# LED_48.net
KiCad netlist of a schematic drawn in Altium Designer
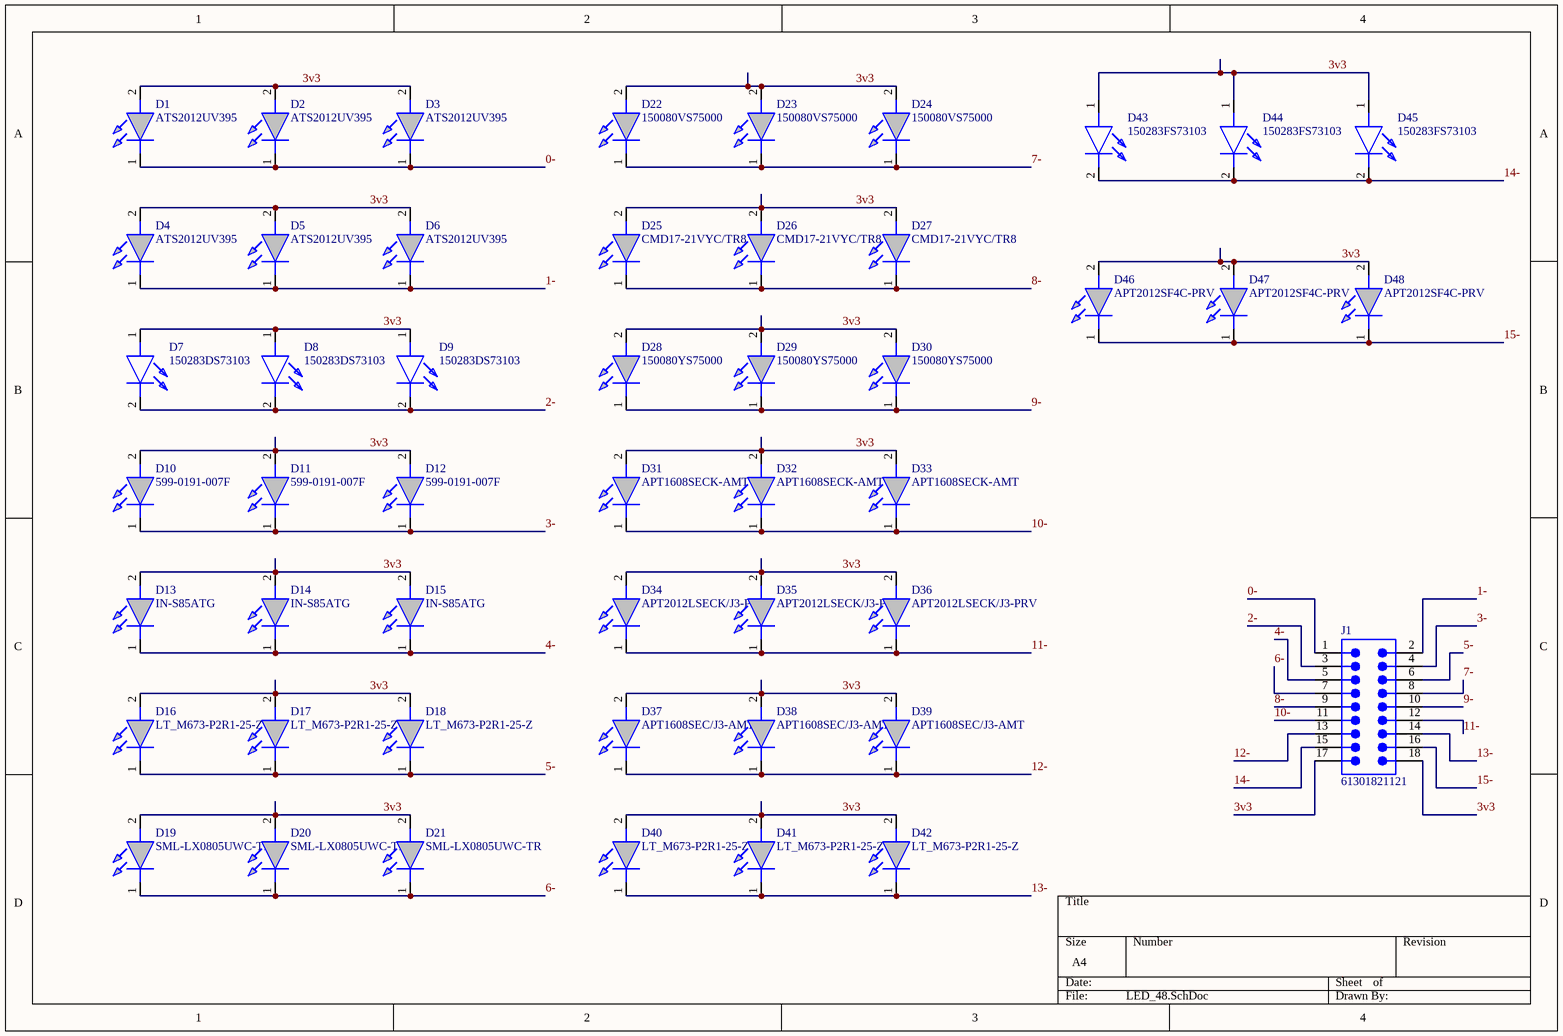
[diagram p0: LED_48.SchDoc]

(export (version "E")
  (design (tool "Eeschema 10.0.6"))
  (components
    (comp (ref "D1")
      (value "ATS2012UV395")
      (footprint "ATS2012UV395")
      (description "Standard LEDs - SMD 2x1.2mm UV SMD")
      (fields (field (name "MOUSER PART NUMBER") "604-ATS2012UV395"))
      (libsource (lib "Schlib2") (part "ATS2012UV395"))
    )
    (comp (ref "D2")
      (value "ATS2012UV395")
      (footprint "ATS2012UV395")
      (description "Standard LEDs - SMD 2x1.2mm UV SMD")
      (fields (field (name "MOUSER PART NUMBER") "604-ATS2012UV395"))
      (libsource (lib "Schlib2") (part "ATS2012UV395"))
    )
    (comp (ref "D3")
      (value "ATS2012UV395")
      (footprint "ATS2012UV395")
      (description "Standard LEDs - SMD 2x1.2mm UV SMD")
      (fields (field (name "MOUSER PART NUMBER") "604-ATS2012UV395"))
      (libsource (lib "Schlib2") (part "ATS2012UV395"))
    )
    (comp (ref "D4")
      (value "ATS2012UV395")
      (footprint "ATS2012UV395")
      (description "Standard LEDs - SMD 2x1.2mm UV SMD")
      (fields (field (name "MOUSER PART NUMBER") "604-ATS2012UV395"))
      (libsource (lib "Schlib2") (part "ATS2012UV395"))
    )
    (comp (ref "D5")
      (value "ATS2012UV395")
      (footprint "ATS2012UV395")
      (description "Standard LEDs - SMD 2x1.2mm UV SMD")
      (fields (field (name "MOUSER PART NUMBER") "604-ATS2012UV395"))
      (libsource (lib "Schlib2") (part "ATS2012UV395"))
    )
    (comp (ref "D6")
      (value "ATS2012UV395")
      (footprint "ATS2012UV395")
      (description "Standard LEDs - SMD 2x1.2mm UV SMD")
      (fields (field (name "MOUSER PART NUMBER") "604-ATS2012UV395"))
      (libsource (lib "Schlib2") (part "ATS2012UV395"))
    )
    (comp (ref "D7")
      (value "150283DS73103")
      (footprint "150283DS73103")
      (description "LED")
      (fields (field (name "MOUSER PART NUMBER") "710-150283DS73103"))
      (libsource (lib "LED_Schlib1") (part "150283DS73103"))
    )
    (comp (ref "D8")
      (value "150283DS73103")
      (footprint "150283DS73103")
      (description "LED")
      (fields (field (name "MOUSER PART NUMBER") "710-150283DS73103"))
      (libsource (lib "LED_Schlib1") (part "150283DS73103"))
    )
    (comp (ref "D9")
      (value "150283DS73103")
      (footprint "150283DS73103")
      (description "LED")
      (fields (field (name "MOUSER PART NUMBER") "710-150283DS73103"))
      (libsource (lib "LED_Schlib1") (part "150283DS73103"))
    )
    (comp (ref "D10")
      (value "599-0191-007F")
      (footprint "LEDC2012X90N")
      (description "Standard LEDs - SMD SMD 0805 BLUE")
      (fields (field (name "MOUSER PART NUMBER") "645-599-0191-007F"))
      (libsource (lib "Schlib2") (part "599-0191-007F"))
    )
    (comp (ref "D11")
      (value "599-0191-007F")
      (footprint "LEDC2012X90N")
      (description "Standard LEDs - SMD SMD 0805 BLUE")
      (fields (field (name "MOUSER PART NUMBER") "645-599-0191-007F"))
      (libsource (lib "Schlib2") (part "599-0191-007F"))
    )
    (comp (ref "D12")
      (value "599-0191-007F")
      (footprint "LEDC2012X90N")
      (description "Standard LEDs - SMD SMD 0805 BLUE")
      (fields (field (name "MOUSER PART NUMBER") "645-599-0191-007F"))
      (libsource (lib "Schlib2") (part "599-0191-007F"))
    )
    (comp (ref "D13")
      (value "IN-S85ATG")
      (footprint "LEDC2012X110N")
      (description "Standard LEDs - SMD True Green LED")
      (fields (field (name "MOUSER PART NUMBER") "743-IN-S85ATG"))
      (libsource (lib "Schlib2") (part "IN-S85ATG"))
    )
    (comp (ref "D14")
      (value "IN-S85ATG")
      (footprint "LEDC2012X110N")
      (description "Standard LEDs - SMD True Green LED")
      (fields (field (name "MOUSER PART NUMBER") "743-IN-S85ATG"))
      (libsource (lib "Schlib2") (part "IN-S85ATG"))
    )
    (comp (ref "D15")
      (value "IN-S85ATG")
      (footprint "LEDC2012X110N")
      (description "Standard LEDs - SMD True Green LED")
      (fields (field (name "MOUSER PART NUMBER") "743-IN-S85ATG"))
      (libsource (lib "Schlib2") (part "IN-S85ATG"))
    )
    (comp (ref "D16")
      (value "LT_M673-P2R1-25-Z")
      (footprint "LEDM2214X140N")
      (description "Standard LEDs - SMD True Green, 532nm 140mcd, 10mA")
      (fields
        (field (name "MOUSER PART NUMBER") "720-LTM673P2R125Z")
        (field (name "MANUFACTURER_PART_NUMBER") "LT M673-P2R1-25-Z")
      )
      (libsource (lib "Schlib2") (part "LT_M673-P2R1-25-Z"))
    )
    (comp (ref "D17")
      (value "LT_M673-P2R1-25-Z")
      (footprint "LEDM2214X140N")
      (description "Standard LEDs - SMD True Green, 532nm 140mcd, 10mA")
      (fields
        (field (name "MOUSER PART NUMBER") "720-LTM673P2R125Z")
        (field (name "MANUFACTURER_PART_NUMBER") "LT M673-P2R1-25-Z")
      )
      (libsource (lib "Schlib2") (part "LT_M673-P2R1-25-Z"))
    )
    (comp (ref "D18")
      (value "LT_M673-P2R1-25-Z")
      (footprint "LEDM2214X140N")
      (description "Standard LEDs - SMD True Green, 532nm 140mcd, 10mA")
      (fields
        (field (name "MOUSER PART NUMBER") "720-LTM673P2R125Z")
        (field (name "MANUFACTURER_PART_NUMBER") "LT M673-P2R1-25-Z")
      )
      (libsource (lib "Schlib2") (part "LT_M673-P2R1-25-Z"))
    )
    (comp (ref "D19")
      (value "SML-LX0805UWC-TR")
      (footprint "LEDC2012X80N")
      (description "Standard LEDs - SMD White, Water Clear 3.5V, 150mcd")
      (fields
        (field (name "MOUSER PART NUMBER") "645-599-0191-007F")
        (field (name "MANUFACTURER_PART_NUMBER") "599-0191-007F")
      )
      (libsource (lib "Schlib2") (part "SML-LX0805UWC-TR"))
    )
    (comp (ref "D20")
      (value "SML-LX0805UWC-TR")
      (footprint "LEDC2012X80N")
      (description "Standard LEDs - SMD White, Water Clear 3.5V, 150mcd")
      (fields
        (field (name "MOUSER PART NUMBER") "645-599-0191-007F")
        (field (name "MANUFACTURER_PART_NUMBER") "599-0191-007F")
      )
      (libsource (lib "Schlib2") (part "SML-LX0805UWC-TR"))
    )
    (comp (ref "D21")
      (value "SML-LX0805UWC-TR")
      (footprint "LEDC2012X80N")
      (description "Standard LEDs - SMD White, Water Clear 3.5V, 150mcd")
      (fields
        (field (name "MOUSER PART NUMBER") "645-599-0191-007F")
        (field (name "MANUFACTURER_PART_NUMBER") "599-0191-007F")
      )
      (libsource (lib "Schlib2") (part "SML-LX0805UWC-TR"))
    )
    (comp (ref "D22")
      (value "150080VS75000")
      (footprint "LEDC2012X80N")
      (description "Standard LEDs - SMD WL-SMCW SMDMono TpVw Waterclr 0805 BrtGrn")
      (fields
        (field (name "MOUSER PART NUMBER") "645-599-0191-007F")
        (field (name "MANUFACTURER_PART_NUMBER") "599-0191-007F")
      )
      (libsource (lib "Schlib2") (part "150080VS75000"))
    )
    (comp (ref "D23")
      (value "150080VS75000")
      (footprint "LEDC2012X80N")
      (description "Standard LEDs - SMD WL-SMCW SMDMono TpVw Waterclr 0805 BrtGrn")
      (fields
        (field (name "MOUSER PART NUMBER") "645-599-0191-007F")
        (field (name "MANUFACTURER_PART_NUMBER") "599-0191-007F")
      )
      (libsource (lib "Schlib2") (part "150080VS75000"))
    )
    (comp (ref "D24")
      (value "150080VS75000")
      (footprint "LEDC2012X80N")
      (description "Standard LEDs - SMD WL-SMCW SMDMono TpVw Waterclr 0805 BrtGrn")
      (fields
        (field (name "MOUSER PART NUMBER") "645-599-0191-007F")
        (field (name "MANUFACTURER_PART_NUMBER") "599-0191-007F")
      )
      (libsource (lib "Schlib2") (part "150080VS75000"))
    )
    (comp (ref "D25")
      (value "CMD17-21VYC/TR8")
      (footprint "LEDC2012X120N")
      (description "Standard LEDs - SMD YELLOW WATER CLEAR")
      (fields
        (field (name "MOUSER PART NUMBER") "645-599-0191-007F")
        (field (name "MANUFACTURER_PART_NUMBER") "599-0191-007F")
      )
      (libsource (lib "Schlib2") (part "CMD17-21VYC/TR8"))
    )
    (comp (ref "D26")
      (value "CMD17-21VYC/TR8")
      (footprint "LEDC2012X120N")
      (description "Standard LEDs - SMD YELLOW WATER CLEAR")
      (fields
        (field (name "MOUSER PART NUMBER") "645-599-0191-007F")
        (field (name "MANUFACTURER_PART_NUMBER") "599-0191-007F")
      )
      (libsource (lib "Schlib2") (part "CMD17-21VYC/TR8"))
    )
    (comp (ref "D27")
      (value "CMD17-21VYC/TR8")
      (footprint "LEDC2012X120N")
      (description "Standard LEDs - SMD YELLOW WATER CLEAR")
      (fields
        (field (name "MOUSER PART NUMBER") "645-599-0191-007F")
        (field (name "MANUFACTURER_PART_NUMBER") "599-0191-007F")
      )
      (libsource (lib "Schlib2") (part "CMD17-21VYC/TR8"))
    )
    (comp (ref "D28")
      (value "150080YS75000")
      (footprint "LEDC2012X80N")
      (description "Standard LEDs - SMD WL-SMCW SMDMono TpVw Waterclr 0805 Yellow")
      (fields
        (field (name "MOUSER PART NUMBER") "645-599-0191-007F")
        (field (name "MANUFACTURER_PART_NUMBER") "599-0191-007F")
      )
      (libsource (lib "Schlib2") (part "SML-LX0805UWC-TR"))
    )
    (comp (ref "D29")
      (value "150080YS75000")
      (footprint "LEDC2012X80N")
      (description "Standard LEDs - SMD WL-SMCW SMDMono TpVw Waterclr 0805 Yellow")
      (fields
        (field (name "MOUSER PART NUMBER") "645-599-0191-007F")
        (field (name "MANUFACTURER_PART_NUMBER") "599-0191-007F")
      )
      (libsource (lib "Schlib2") (part "SML-LX0805UWC-TR"))
    )
    (comp (ref "D30")
      (value "150080YS75000")
      (footprint "LEDC2012X80N")
      (description "Standard LEDs - SMD WL-SMCW SMDMono TpVw Waterclr 0805 Yellow")
      (fields
        (field (name "MOUSER PART NUMBER") "645-599-0191-007F")
        (field (name "MANUFACTURER_PART_NUMBER") "599-0191-007F")
      )
      (libsource (lib "Schlib2") (part "SML-LX0805UWC-TR"))
    )
    (comp (ref "D31")
      (value "APT1608SECK-AMT")
      (footprint "LEDC1608X85N")
      (description "Standard LEDs - SMD 1.6x0.8mm Orange")
      (fields
        (field (name "MOUSER PART NUMBER") "645-599-0191-007F")
        (field (name "MANUFACTURER_PART_NUMBER") "599-0191-007F")
      )
      (libsource (lib "Schlib2") (part "APT1608SECK-AMT"))
    )
    (comp (ref "D32")
      (value "APT1608SECK-AMT")
      (footprint "LEDC1608X85N")
      (description "Standard LEDs - SMD 1.6x0.8mm Orange")
      (fields
        (field (name "MOUSER PART NUMBER") "645-599-0191-007F")
        (field (name "MANUFACTURER_PART_NUMBER") "599-0191-007F")
      )
      (libsource (lib "Schlib2") (part "APT1608SECK-AMT"))
    )
    (comp (ref "D33")
      (value "APT1608SECK-AMT")
      (footprint "LEDC1608X85N")
      (description "Standard LEDs - SMD 1.6x0.8mm Orange")
      (fields
        (field (name "MOUSER PART NUMBER") "645-599-0191-007F")
        (field (name "MANUFACTURER_PART_NUMBER") "599-0191-007F")
      )
      (libsource (lib "Schlib2") (part "APT1608SECK-AMT"))
    )
    (comp (ref "D34")
      (value "APT2012LSECK/J3-PRV")
      (footprint "LEDC2012X75N")
      (description "Standard LEDs - SMD 2.0X1.2MM LOW CRNT")
      (fields
        (field (name "MANUFACTURER_PART_NUMBER") "ATS2012UV395")
        (field (name "MOUSER PART NUMBER") "604-ATS2012UV395")
      )
      (libsource (lib "Schlib2") (part "APT2012LSECK/J3-PRV"))
    )
    (comp (ref "D35")
      (value "APT2012LSECK/J3-PRV")
      (footprint "LEDC2012X75N")
      (description "Standard LEDs - SMD 2.0X1.2MM LOW CRNT")
      (fields
        (field (name "MANUFACTURER_PART_NUMBER") "ATS2012UV395")
        (field (name "MOUSER PART NUMBER") "604-ATS2012UV395")
      )
      (libsource (lib "Schlib2") (part "APT2012LSECK/J3-PRV"))
    )
    (comp (ref "D36")
      (value "APT2012LSECK/J3-PRV")
      (footprint "LEDC2012X75N")
      (description "Standard LEDs - SMD 2.0X1.2MM LOW CRNT")
      (fields
        (field (name "MANUFACTURER_PART_NUMBER") "ATS2012UV395")
        (field (name "MOUSER PART NUMBER") "604-ATS2012UV395")
      )
      (libsource (lib "Schlib2") (part "APT2012LSECK/J3-PRV"))
    )
    (comp (ref "D37")
      (value "APT1608SEC/J3-AMT")
      (footprint "APT1608SECJ3AMT")
      (description "Standard LEDs - SMD 1.6x0.8mm Red")
      (fields
        (field (name "MANUFACTURER_PART_NUMBER") "ATS2012UV395")
        (field (name "MOUSER PART NUMBER") "604-ATS2012UV395")
      )
      (libsource (lib "Schlib2") (part "APT1608SEC/J3-AMT"))
    )
    (comp (ref "D38")
      (value "APT1608SEC/J3-AMT")
      (footprint "APT1608SECJ3AMT")
      (description "Standard LEDs - SMD 1.6x0.8mm Red")
      (fields
        (field (name "MANUFACTURER_PART_NUMBER") "ATS2012UV395")
        (field (name "MOUSER PART NUMBER") "604-ATS2012UV395")
      )
      (libsource (lib "Schlib2") (part "APT1608SEC/J3-AMT"))
    )
    (comp (ref "D39")
      (value "APT1608SEC/J3-AMT")
      (footprint "APT1608SECJ3AMT")
      (description "Standard LEDs - SMD 1.6x0.8mm Red")
      (fields
        (field (name "MANUFACTURER_PART_NUMBER") "ATS2012UV395")
        (field (name "MOUSER PART NUMBER") "604-ATS2012UV395")
      )
      (libsource (lib "Schlib2") (part "APT1608SEC/J3-AMT"))
    )
    (comp (ref "D40")
      (value "LT_M673-P2R1-25-Z")
      (footprint "LEDM2214X140N")
      (description "Standard LEDs - SMD True Green, 532nm 140mcd, 10mA")
      (fields
        (field (name "MOUSER PART NUMBER") "720-LTM673P2R125Z")
        (field (name "MANUFACTURER_PART_NUMBER") "LT M673-P2R1-25-Z")
      )
      (libsource (lib "Schlib2") (part "LT_M673-P2R1-25-Z"))
    )
    (comp (ref "D41")
      (value "LT_M673-P2R1-25-Z")
      (footprint "LEDM2214X140N")
      (description "Standard LEDs - SMD True Green, 532nm 140mcd, 10mA")
      (fields
        (field (name "MOUSER PART NUMBER") "720-LTM673P2R125Z")
        (field (name "MANUFACTURER_PART_NUMBER") "LT M673-P2R1-25-Z")
      )
      (libsource (lib "Schlib2") (part "LT_M673-P2R1-25-Z"))
    )
    (comp (ref "D42")
      (value "LT_M673-P2R1-25-Z")
      (footprint "LEDM2214X140N")
      (description "Standard LEDs - SMD True Green, 532nm 140mcd, 10mA")
      (fields
        (field (name "MOUSER PART NUMBER") "720-LTM673P2R125Z")
        (field (name "MANUFACTURER_PART_NUMBER") "LT M673-P2R1-25-Z")
      )
      (libsource (lib "Schlib2") (part "LT_M673-P2R1-25-Z"))
    )
    (comp (ref "D43")
      (value "150283FS73103")
      (footprint "150283DS73103")
      (description "LED")
      (fields
        (field (name "MANUFACTURER_PART_NUMBER") "150283DS73103")
        (field (name "MOUSER PART NUMBER") "710-150283DS73103")
      )
      (libsource (lib "LED_Schlib1") (part "150283DS73103"))
    )
    (comp (ref "D44")
      (value "150283FS73103")
      (footprint "150283DS73103")
      (description "LED")
      (fields
        (field (name "MANUFACTURER_PART_NUMBER") "150283DS73103")
        (field (name "MOUSER PART NUMBER") "710-150283DS73103")
      )
      (libsource (lib "LED_Schlib1") (part "150283DS73103"))
    )
    (comp (ref "D45")
      (value "150283FS73103")
      (footprint "150283DS73103")
      (description "LED")
      (fields
        (field (name "MANUFACTURER_PART_NUMBER") "150283DS73103")
        (field (name "MOUSER PART NUMBER") "710-150283DS73103")
      )
      (libsource (lib "LED_Schlib1") (part "150283DS73103"))
    )
    (comp (ref "D46")
      (value "APT2012SF4C-PRV")
      (footprint "LEDC2012X85N")
      (description "Infrared Emitters IR 880nm 120 deg Water Clear 1 mW/sr")
      (fields
        (field (name "MANUFACTURER_PART_NUMBER") "ATS2012UV395")
        (field (name "MOUSER PART NUMBER") "604-ATS2012UV395")
      )
      (libsource (lib "Schlib2") (part "APT2012SF4C-PRV"))
    )
    (comp (ref "D47")
      (value "APT2012SF4C-PRV")
      (footprint "LEDC2012X85N")
      (description "Infrared Emitters IR 880nm 120 deg Water Clear 1 mW/sr")
      (fields
        (field (name "MANUFACTURER_PART_NUMBER") "ATS2012UV395")
        (field (name "MOUSER PART NUMBER") "604-ATS2012UV395")
      )
      (libsource (lib "Schlib2") (part "APT2012SF4C-PRV"))
    )
    (comp (ref "D48")
      (value "APT2012SF4C-PRV")
      (footprint "LEDC2012X85N")
      (description "Infrared Emitters IR 880nm 120 deg Water Clear 1 mW/sr")
      (fields
        (field (name "MANUFACTURER_PART_NUMBER") "ATS2012UV395")
        (field (name "MOUSER PART NUMBER") "604-ATS2012UV395")
      )
      (libsource (lib "Schlib2") (part "APT2012SF4C-PRV"))
    )
    (comp (ref "J1")
      (value "61301821121")
      (footprint "61301821121")
      (libsource (lib "Altium Content Vault") (part "Header_Male_2R_18P"))
    )
  )
  (nets
    (net (code "1") (name "/0-") (class "Default")
      (node (ref "D1") (pin "1") (pinfunction "K_1") (pintype "passive"))
      (node (ref "D2") (pin "1") (pinfunction "K_1") (pintype "passive"))
      (node (ref "D3") (pin "1") (pinfunction "K_1") (pintype "passive"))
      (node (ref "J1") (pin "1") (pinfunction "1_1") (pintype "passive"))
    )
    (net (code "2") (name "/1-") (class "Default")
      (node (ref "D4") (pin "1") (pinfunction "K_1") (pintype "passive"))
      (node (ref "D5") (pin "1") (pinfunction "K_1") (pintype "passive"))
      (node (ref "D6") (pin "1") (pinfunction "K_1") (pintype "passive"))
      (node (ref "J1") (pin "2") (pinfunction "2_2") (pintype "passive"))
    )
    (net (code "3") (name "/2-") (class "Default")
      (node (ref "D7") (pin "2") (pinfunction "K_2") (pintype "passive"))
      (node (ref "D8") (pin "2") (pinfunction "K_2") (pintype "passive"))
      (node (ref "D9") (pin "2") (pinfunction "K_2") (pintype "passive"))
      (node (ref "J1") (pin "3") (pinfunction "3_3") (pintype "passive"))
    )
    (net (code "4") (name "/3-") (class "Default")
      (node (ref "D10") (pin "1") (pinfunction "K_1") (pintype "passive"))
      (node (ref "D11") (pin "1") (pinfunction "K_1") (pintype "passive"))
      (node (ref "D12") (pin "1") (pinfunction "K_1") (pintype "passive"))
      (node (ref "J1") (pin "4") (pinfunction "4_4") (pintype "passive"))
    )
    (net (code "5") (name "/3v3") (class "Default")
      (node (ref "D1") (pin "2") (pinfunction "A_2") (pintype "passive"))
      (node (ref "D10") (pin "2") (pinfunction "A_2") (pintype "passive"))
      (node (ref "D11") (pin "2") (pinfunction "A_2") (pintype "passive"))
      (node (ref "D12") (pin "2") (pinfunction "A_2") (pintype "passive"))
      (node (ref "D13") (pin "2") (pinfunction "A_2") (pintype "passive"))
      (node (ref "D14") (pin "2") (pinfunction "A_2") (pintype "passive"))
      (node (ref "D15") (pin "2") (pinfunction "A_2") (pintype "passive"))
      (node (ref "D16") (pin "2") (pinfunction "A_2") (pintype "passive"))
      (node (ref "D17") (pin "2") (pinfunction "A_2") (pintype "passive"))
      (node (ref "D18") (pin "2") (pinfunction "A_2") (pintype "passive"))
      (node (ref "D19") (pin "2") (pinfunction "A_2") (pintype "passive"))
      (node (ref "D2") (pin "2") (pinfunction "A_2") (pintype "passive"))
      (node (ref "D20") (pin "2") (pinfunction "A_2") (pintype "passive"))
      (node (ref "D21") (pin "2") (pinfunction "A_2") (pintype "passive"))
      (node (ref "D22") (pin "2") (pinfunction "A_2") (pintype "passive"))
      (node (ref "D23") (pin "2") (pinfunction "A_2") (pintype "passive"))
      (node (ref "D24") (pin "2") (pinfunction "A_2") (pintype "passive"))
      (node (ref "D25") (pin "2") (pinfunction "A_2") (pintype "passive"))
      (node (ref "D26") (pin "2") (pinfunction "A_2") (pintype "passive"))
      (node (ref "D27") (pin "2") (pinfunction "A_2") (pintype "passive"))
      (node (ref "D28") (pin "2") (pinfunction "A_2") (pintype "passive"))
      (node (ref "D29") (pin "2") (pinfunction "A_2") (pintype "passive"))
      (node (ref "D3") (pin "2") (pinfunction "A_2") (pintype "passive"))
      (node (ref "D30") (pin "2") (pinfunction "A_2") (pintype "passive"))
      (node (ref "D31") (pin "2") (pinfunction "A_2") (pintype "passive"))
      (node (ref "D32") (pin "2") (pinfunction "A_2") (pintype "passive"))
      (node (ref "D33") (pin "2") (pinfunction "A_2") (pintype "passive"))
      (node (ref "D34") (pin "2") (pinfunction "A_2") (pintype "passive"))
      (node (ref "D35") (pin "2") (pinfunction "A_2") (pintype "passive"))
      (node (ref "D36") (pin "2") (pinfunction "A_2") (pintype "passive"))
      (node (ref "D37") (pin "2") (pinfunction "A_2") (pintype "passive"))
      (node (ref "D38") (pin "2") (pinfunction "A_2") (pintype "passive"))
      (node (ref "D39") (pin "2") (pinfunction "A_2") (pintype "passive"))
      (node (ref "D4") (pin "2") (pinfunction "A_2") (pintype "passive"))
      (node (ref "D40") (pin "2") (pinfunction "A_2") (pintype "passive"))
      (node (ref "D41") (pin "2") (pinfunction "A_2") (pintype "passive"))
      (node (ref "D42") (pin "2") (pinfunction "A_2") (pintype "passive"))
      (node (ref "D43") (pin "1") (pinfunction "A_1") (pintype "passive"))
      (node (ref "D44") (pin "1") (pinfunction "A_1") (pintype "passive"))
      (node (ref "D45") (pin "1") (pinfunction "A_1") (pintype "passive"))
      (node (ref "D46") (pin "2") (pinfunction "A_2") (pintype "passive"))
      (node (ref "D47") (pin "2") (pinfunction "A_2") (pintype "passive"))
      (node (ref "D48") (pin "2") (pinfunction "A_2") (pintype "passive"))
      (node (ref "D5") (pin "2") (pinfunction "A_2") (pintype "passive"))
      (node (ref "D6") (pin "2") (pinfunction "A_2") (pintype "passive"))
      (node (ref "D7") (pin "1") (pinfunction "A_1") (pintype "passive"))
      (node (ref "D8") (pin "1") (pinfunction "A_1") (pintype "passive"))
      (node (ref "D9") (pin "1") (pinfunction "A_1") (pintype "passive"))
      (node (ref "J1") (pin "17") (pinfunction "17_17") (pintype "passive"))
      (node (ref "J1") (pin "18") (pinfunction "18_18") (pintype "passive"))
    )
    (net (code "6") (name "/4-") (class "Default")
      (node (ref "D13") (pin "1") (pinfunction "K_1") (pintype "passive"))
      (node (ref "D14") (pin "1") (pinfunction "K_1") (pintype "passive"))
      (node (ref "D15") (pin "1") (pinfunction "K_1") (pintype "passive"))
      (node (ref "J1") (pin "5") (pinfunction "5_5") (pintype "passive"))
    )
    (net (code "7") (name "/5-") (class "Default")
      (node (ref "D16") (pin "1") (pinfunction "K_1") (pintype "passive"))
      (node (ref "D17") (pin "1") (pinfunction "K_1") (pintype "passive"))
      (node (ref "D18") (pin "1") (pinfunction "K_1") (pintype "passive"))
      (node (ref "J1") (pin "6") (pinfunction "6_6") (pintype "passive"))
    )
    (net (code "8") (name "/6-") (class "Default")
      (node (ref "D19") (pin "1") (pinfunction "K_1") (pintype "passive"))
      (node (ref "D20") (pin "1") (pinfunction "K_1") (pintype "passive"))
      (node (ref "D21") (pin "1") (pinfunction "K_1") (pintype "passive"))
      (node (ref "J1") (pin "7") (pinfunction "7_7") (pintype "passive"))
    )
    (net (code "9") (name "/7-") (class "Default")
      (node (ref "D22") (pin "1") (pinfunction "K_1") (pintype "passive"))
      (node (ref "D23") (pin "1") (pinfunction "K_1") (pintype "passive"))
      (node (ref "D24") (pin "1") (pinfunction "K_1") (pintype "passive"))
      (node (ref "J1") (pin "8") (pinfunction "8_8") (pintype "passive"))
    )
    (net (code "10") (name "/8-") (class "Default")
      (node (ref "D25") (pin "1") (pinfunction "K_1") (pintype "passive"))
      (node (ref "D26") (pin "1") (pinfunction "K_1") (pintype "passive"))
      (node (ref "D27") (pin "1") (pinfunction "K_1") (pintype "passive"))
      (node (ref "J1") (pin "9") (pinfunction "9_9") (pintype "passive"))
    )
    (net (code "11") (name "/9-") (class "Default")
      (node (ref "D28") (pin "1") (pinfunction "K_1") (pintype "passive"))
      (node (ref "D29") (pin "1") (pinfunction "K_1") (pintype "passive"))
      (node (ref "D30") (pin "1") (pinfunction "K_1") (pintype "passive"))
      (node (ref "J1") (pin "10") (pinfunction "10_10") (pintype "passive"))
    )
    (net (code "12") (name "/10-") (class "Default")
      (node (ref "D31") (pin "1") (pinfunction "K_1") (pintype "passive"))
      (node (ref "D32") (pin "1") (pinfunction "K_1") (pintype "passive"))
      (node (ref "D33") (pin "1") (pinfunction "K_1") (pintype "passive"))
      (node (ref "J1") (pin "11") (pinfunction "11_11") (pintype "passive"))
    )
    (net (code "13") (name "/11-") (class "Default")
      (node (ref "D34") (pin "1") (pinfunction "K_1") (pintype "passive"))
      (node (ref "D35") (pin "1") (pinfunction "K_1") (pintype "passive"))
      (node (ref "D36") (pin "1") (pinfunction "K_1") (pintype "passive"))
      (node (ref "J1") (pin "12") (pinfunction "12_12") (pintype "passive"))
    )
    (net (code "14") (name "/12-") (class "Default")
      (node (ref "D37") (pin "1") (pinfunction "K_1") (pintype "passive"))
      (node (ref "D38") (pin "1") (pinfunction "K_1") (pintype "passive"))
      (node (ref "D39") (pin "1") (pinfunction "K_1") (pintype "passive"))
      (node (ref "J1") (pin "13") (pinfunction "13_13") (pintype "passive"))
    )
    (net (code "15") (name "/13-") (class "Default")
      (node (ref "D40") (pin "1") (pinfunction "K_1") (pintype "passive"))
      (node (ref "D41") (pin "1") (pinfunction "K_1") (pintype "passive"))
      (node (ref "D42") (pin "1") (pinfunction "K_1") (pintype "passive"))
      (node (ref "J1") (pin "14") (pinfunction "14_14") (pintype "passive"))
    )
    (net (code "16") (name "/14-") (class "Default")
      (node (ref "D43") (pin "2") (pinfunction "K_2") (pintype "passive"))
      (node (ref "D44") (pin "2") (pinfunction "K_2") (pintype "passive"))
      (node (ref "D45") (pin "2") (pinfunction "K_2") (pintype "passive"))
      (node (ref "J1") (pin "15") (pinfunction "15_15") (pintype "passive"))
    )
    (net (code "17") (name "/15-") (class "Default")
      (node (ref "D46") (pin "1") (pinfunction "K_1") (pintype "passive"))
      (node (ref "D47") (pin "1") (pinfunction "K_1") (pintype "passive"))
      (node (ref "D48") (pin "1") (pinfunction "K_1") (pintype "passive"))
      (node (ref "J1") (pin "16") (pinfunction "16_16") (pintype "passive"))
    )
  )
)
